# main.net
KiCad netlist of a schematic drawn in EAGLE
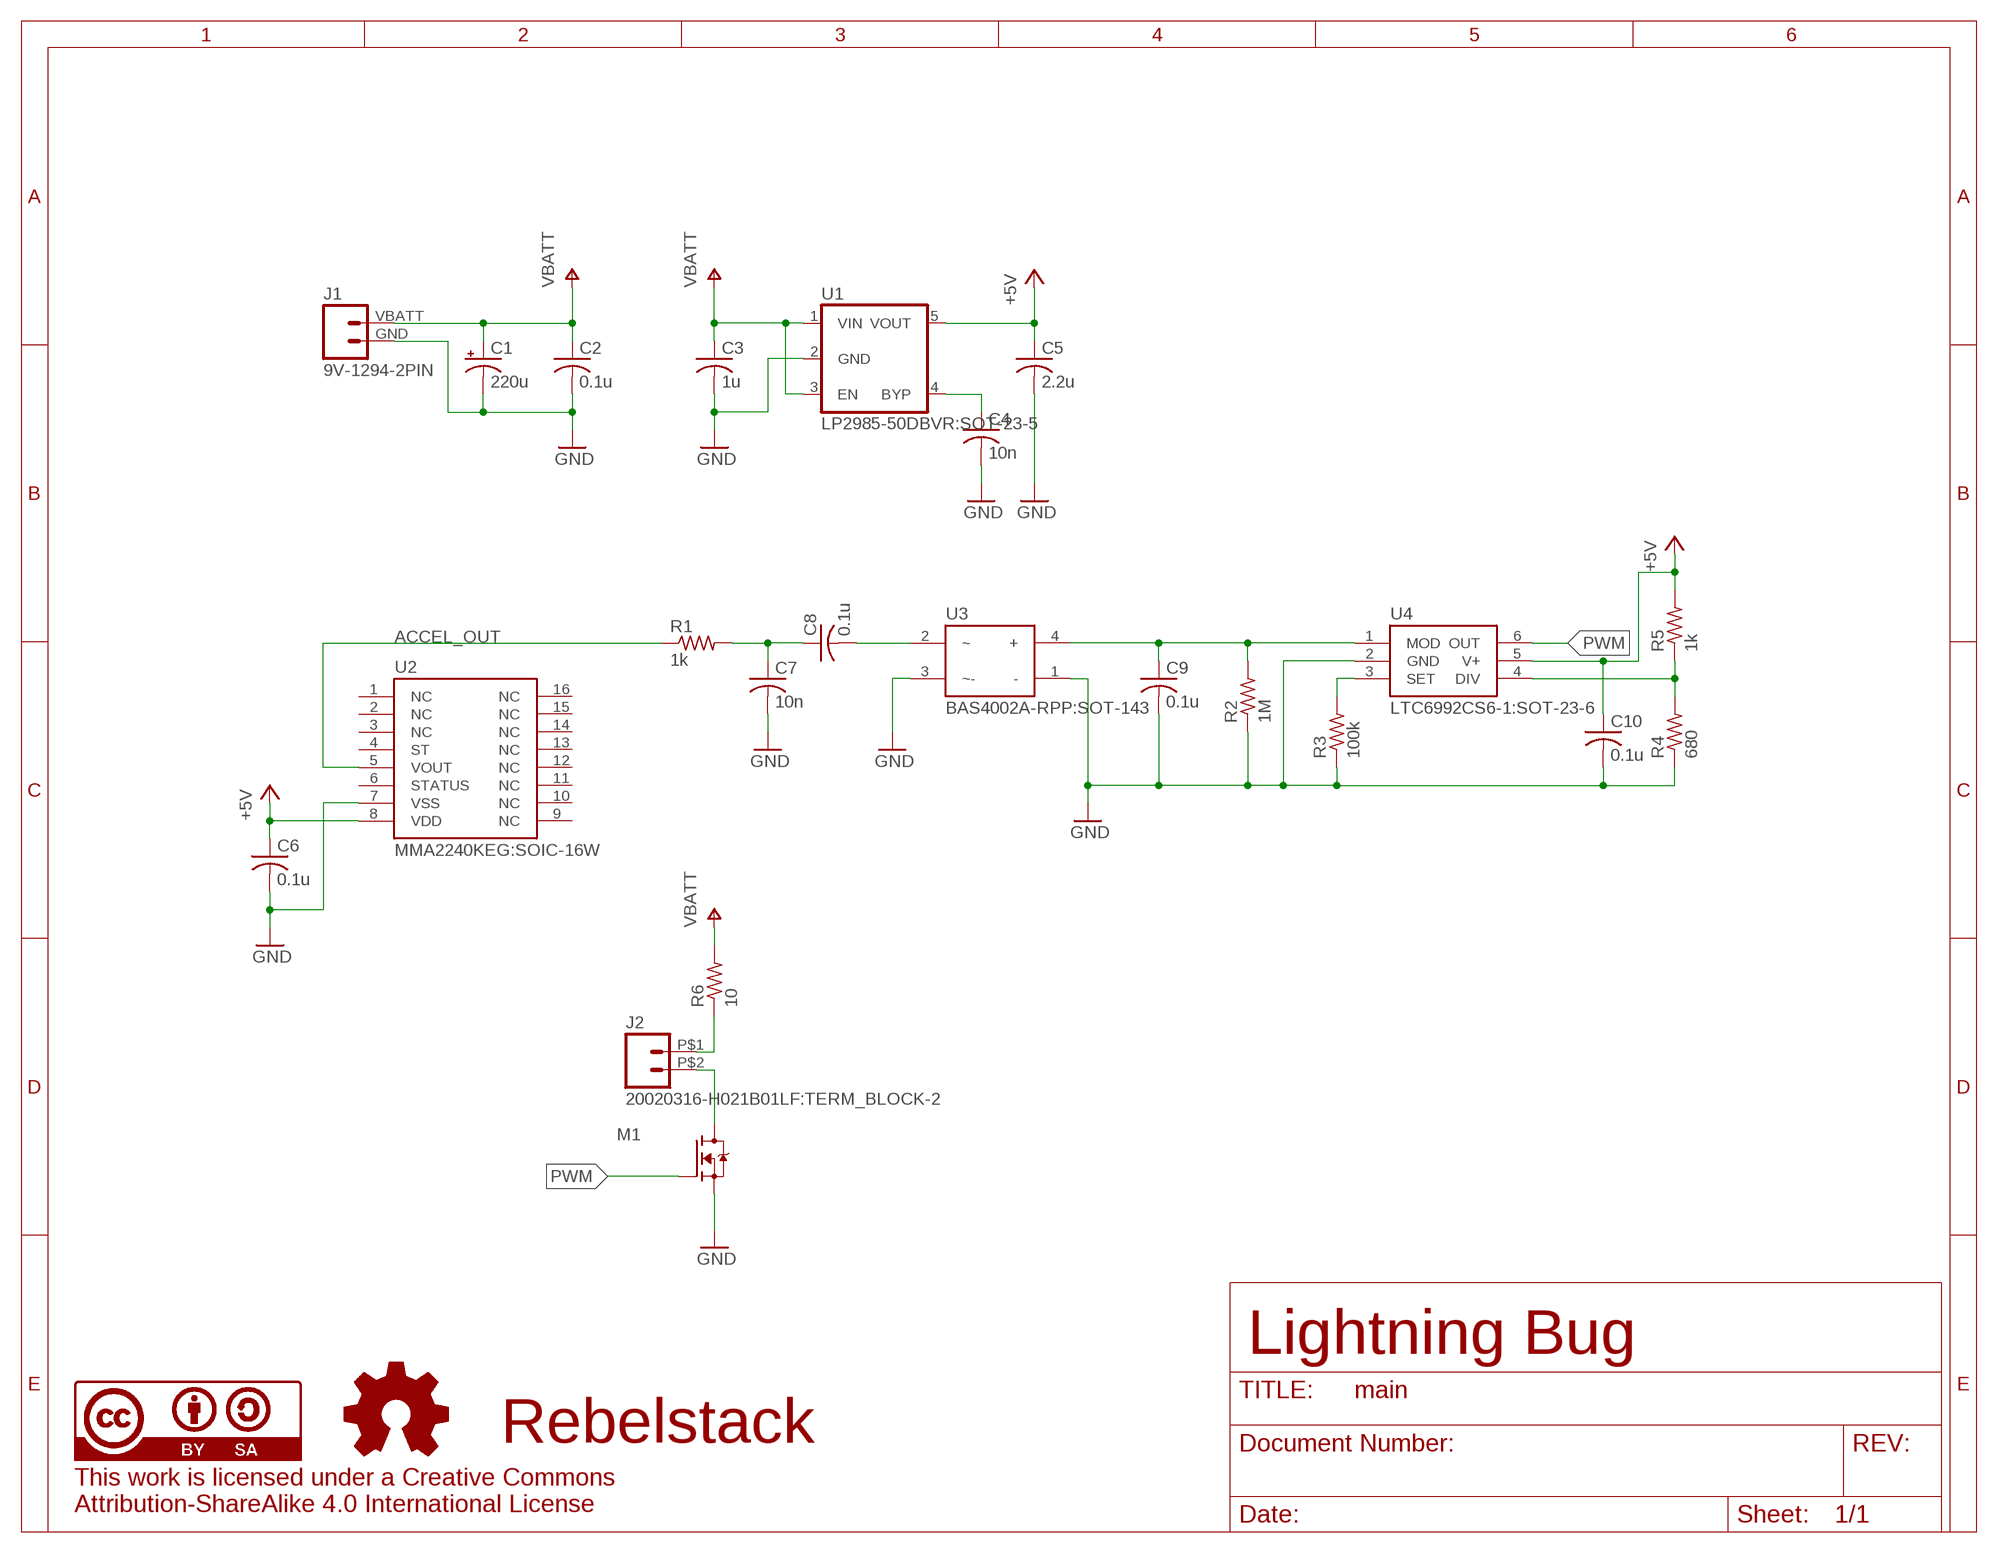
[diagram p0: schematic, sheet 1]

(export (version "E")
  (design (tool "Eeschema 10.0.6"))
  (components
    (comp (ref "C1")
      (value "220u")
      (footprint "eagle-import:D_7343-31W")
      (libsource (lib "eagle-import") (part "CPOL-USD/7343-31W"))
    )
    (comp (ref "C2")
      (value "0.1u")
      (footprint "eagle-import:C0805")
      (libsource (lib "eagle-import") (part "C-USC0805"))
    )
    (comp (ref "C3")
      (value "1u")
      (footprint "eagle-import:C0805")
      (libsource (lib "eagle-import") (part "C-USC0805"))
    )
    (comp (ref "C4")
      (value "10n")
      (footprint "eagle-import:C0805")
      (libsource (lib "eagle-import") (part "C-USC0805"))
    )
    (comp (ref "C5")
      (value "2.2u")
      (footprint "eagle-import:C0805")
      (libsource (lib "eagle-import") (part "C-USC0805"))
    )
    (comp (ref "C6")
      (value "0.1u")
      (footprint "eagle-import:C0805")
      (libsource (lib "eagle-import") (part "C-USC0805"))
    )
    (comp (ref "C7")
      (value "10n")
      (footprint "eagle-import:C0805")
      (libsource (lib "eagle-import") (part "C-USC0805"))
    )
    (comp (ref "C8")
      (value "0.1u")
      (footprint "eagle-import:C0805")
      (libsource (lib "eagle-import") (part "C-USC0805"))
    )
    (comp (ref "C9")
      (value "0.1u")
      (footprint "eagle-import:C0805")
      (libsource (lib "eagle-import") (part "C-USC0805"))
    )
    (comp (ref "C10")
      (value "0.1u")
      (footprint "eagle-import:C0805")
      (libsource (lib "eagle-import") (part "C-USC0805"))
    )
    (comp (ref "J1")
      (value "9V-1294-2PIN")
      (footprint "eagle-import:9V-THRU")
      (libsource (lib "eagle-import") (part "9V-1294-2PIN"))
    )
    (comp (ref "J2")
      (value "20020316-H021B01LF:TERM_BLOCK-2")
      (footprint "eagle-import:TERM_BLOCK-2")
      (libsource (lib "eagle-import") (part "20020316-H021B01LF{colon}TERM_BLOCK-2"))
    )
    (comp (ref "M1")
      (value "IRLML2502TRPBF:SOT-23-3")
      (footprint "eagle-import:SOT-23-3")
      (libsource (lib "eagle-import") (part "IRLML2502TRPBF{colon}SOT-23-3"))
    )
    (comp (ref "R1")
      (value "1k")
      (footprint "eagle-import:M0805")
      (libsource (lib "eagle-import") (part "R-US_M0805"))
    )
    (comp (ref "R2")
      (value "1M")
      (footprint "eagle-import:M0805")
      (libsource (lib "eagle-import") (part "R-US_M0805"))
    )
    (comp (ref "R3")
      (value "100k")
      (footprint "eagle-import:M0805")
      (libsource (lib "eagle-import") (part "R-US_M0805"))
    )
    (comp (ref "R4")
      (value "680")
      (footprint "eagle-import:M0805")
      (libsource (lib "eagle-import") (part "R-US_M0805"))
    )
    (comp (ref "R5")
      (value "1k")
      (footprint "eagle-import:M0805")
      (libsource (lib "eagle-import") (part "R-US_M0805"))
    )
    (comp (ref "R6")
      (value "10")
      (footprint "eagle-import:R2512")
      (libsource (lib "eagle-import") (part "R-US_R2512"))
    )
    (comp (ref "U$4")
      (value "CC-BY-SA-4.0-INT-PCB")
      (footprint "eagle-import:CC-BY-SA-4.0-INT")
      (libsource (lib "eagle-import") (part "CC-BY-SA-4.0-INT-PCB"))
    )
    (comp (ref "U$5")
      (value "OSHW-LOGO-PCB")
      (footprint "eagle-import:OSHW-LOGO")
      (libsource (lib "eagle-import") (part "OSHW-LOGO-PCB"))
    )
    (comp (ref "U1")
      (value "LP2985-50DBVR:SOT-23-5")
      (footprint "eagle-import:SOT-23-5")
      (libsource (lib "eagle-import") (part "LP2985-50DBVR{colon}SOT-23-5"))
    )
    (comp (ref "U2")
      (value "MMA2240KEG:SOIC-16W")
      (footprint "eagle-import:SOIC-16W")
      (libsource (lib "eagle-import") (part "MMA2240KEG{colon}SOIC-16W"))
    )
    (comp (ref "U3")
      (value "BAS4002A-RPP:SOT-143")
      (footprint "eagle-import:SOT-143")
      (libsource (lib "eagle-import") (part "BAS4002A-RPP{colon}SOT-143"))
    )
    (comp (ref "U4")
      (value "LTC6992CS6-1:SOT-23-6")
      (footprint "eagle-import:SOT-23-6")
      (libsource (lib "eagle-import") (part "LTC6992CS6-1{colon}SOT-23-6"))
    )
  )
  (nets
    (net (code "1") (name "+5V") (class "Default")
      (node (ref "C10") (pin "1") (pinfunction "1_1") (pintype "passive"))
      (node (ref "C5") (pin "1") (pinfunction "1_1") (pintype "passive"))
      (node (ref "C6") (pin "1") (pinfunction "1_1") (pintype "passive"))
      (node (ref "R5") (pin "2") (pinfunction "2_2") (pintype "passive"))
      (node (ref "U1") (pin "5") (pinfunction "VOUT_5") (pintype "power_in"))
      (node (ref "U2") (pin "8") (pinfunction "VDD_8") (pintype "passive"))
      (node (ref "U4") (pin "5") (pinfunction "V+_5") (pintype "power_in"))
    )
    (net (code "2") (name "/ACCEL_OUT") (class "Default")
      (node (ref "R1") (pin "1") (pinfunction "1_1") (pintype "passive"))
      (node (ref "U2") (pin "5") (pinfunction "VOUT_5") (pintype "output"))
    )
    (net (code "3") (name "GND") (class "Default")
      (node (ref "C1") (pin "-") (pinfunction "-_-") (pintype "passive"))
      (node (ref "C10") (pin "2") (pinfunction "2_2") (pintype "passive"))
      (node (ref "C2") (pin "2") (pinfunction "2_2") (pintype "passive"))
      (node (ref "C3") (pin "2") (pinfunction "2_2") (pintype "passive"))
      (node (ref "C4") (pin "2") (pinfunction "2_2") (pintype "passive"))
      (node (ref "C5") (pin "2") (pinfunction "2_2") (pintype "passive"))
      (node (ref "C6") (pin "2") (pinfunction "2_2") (pintype "passive"))
      (node (ref "C7") (pin "2") (pinfunction "2_2") (pintype "passive"))
      (node (ref "C9") (pin "2") (pinfunction "2_2") (pintype "passive"))
      (node (ref "J1") (pin "GND") (pinfunction "2_GND") (pintype "power_in"))
      (node (ref "M1") (pin "2") (pinfunction "S_2") (pintype "passive"))
      (node (ref "R2") (pin "1") (pinfunction "1_1") (pintype "passive"))
      (node (ref "R3") (pin "1") (pinfunction "1_1") (pintype "passive"))
      (node (ref "R4") (pin "1") (pinfunction "1_1") (pintype "passive"))
      (node (ref "U1") (pin "2") (pinfunction "GND_2") (pintype "power_in"))
      (node (ref "U2") (pin "7") (pinfunction "VSS_7") (pintype "power_in"))
      (node (ref "U3") (pin "1") (pinfunction "-_1") (pintype "passive"))
      (node (ref "U3") (pin "3") (pinfunction "~{-}_3") (pintype "passive"))
      (node (ref "U4") (pin "2") (pinfunction "GND_2") (pintype "power_in"))
    )
    (net (code "4") (name "Net-(C7-Pad1)") (class "Default")
      (node (ref "C7") (pin "1") (pinfunction "1_1") (pintype "passive"))
      (node (ref "C8") (pin "1") (pinfunction "1_1") (pintype "passive"))
      (node (ref "R1") (pin "2") (pinfunction "2_2") (pintype "passive"))
    )
    (net (code "5") (name "Net-(J2-1)") (class "Default")
      (node (ref "J2") (pin "P$1") (pinfunction "1_P$1") (pintype "passive"))
      (node (ref "R6") (pin "1") (pinfunction "1_1") (pintype "passive"))
    )
    (net (code "6") (name "Net-(J2-2)") (class "Default")
      (node (ref "J2") (pin "P$2") (pinfunction "2_P$2") (pintype "passive"))
      (node (ref "M1") (pin "3") (pinfunction "D_3") (pintype "passive"))
    )
    (net (code "7") (name "Net-(U1-BYP)") (class "Default")
      (node (ref "C4") (pin "1") (pinfunction "1_1") (pintype "passive"))
      (node (ref "U1") (pin "4") (pinfunction "BYP_4") (pintype "passive"))
    )
    (net (code "8") (name "Net-(U3-+)") (class "Default")
      (node (ref "C9") (pin "1") (pinfunction "1_1") (pintype "passive"))
      (node (ref "R2") (pin "2") (pinfunction "2_2") (pintype "passive"))
      (node (ref "U3") (pin "4") (pinfunction "+_4") (pintype "passive"))
      (node (ref "U4") (pin "1") (pinfunction "MOD_1") (pintype "input"))
    )
    (net (code "9") (name "Net-(U3-~)") (class "Default")
      (node (ref "C8") (pin "2") (pinfunction "2_2") (pintype "passive"))
      (node (ref "U3") (pin "2") (pinfunction "~_2") (pintype "passive"))
    )
    (net (code "10") (name "Net-(U4-DIV)") (class "Default")
      (node (ref "R4") (pin "2") (pinfunction "2_2") (pintype "passive"))
      (node (ref "R5") (pin "1") (pinfunction "1_1") (pintype "passive"))
      (node (ref "U4") (pin "4") (pinfunction "DIV_4") (pintype "passive"))
    )
    (net (code "11") (name "Net-(U4-SET)") (class "Default")
      (node (ref "R3") (pin "2") (pinfunction "2_2") (pintype "passive"))
      (node (ref "U4") (pin "3") (pinfunction "SET_3") (pintype "passive"))
    )
    (net (code "12") (name "PWM") (class "Default")
      (node (ref "M1") (pin "1") (pinfunction "G_1") (pintype "passive"))
      (node (ref "U4") (pin "6") (pinfunction "OUT_6") (pintype "output"))
    )
    (net (code "13") (name "VBATT") (class "Default")
      (node (ref "C1") (pin "+") (pinfunction "+_+") (pintype "passive"))
      (node (ref "C2") (pin "1") (pinfunction "1_1") (pintype "passive"))
      (node (ref "C3") (pin "1") (pinfunction "1_1") (pintype "passive"))
      (node (ref "J1") (pin "VBATT") (pinfunction "1_VBATT") (pintype "power_in"))
      (node (ref "R6") (pin "2") (pinfunction "2_2") (pintype "passive"))
      (node (ref "U1") (pin "1") (pinfunction "VIN_1") (pintype "power_in"))
      (node (ref "U1") (pin "3") (pinfunction "EN_3") (pintype "input"))
    )
    (net (code "14") (name "unconnected-(U2-NC-Pad1)") (class "Default")
      (node (ref "U2") (pin "1") (pinfunction "NC_1") (pintype "no_connect"))
    )
    (net (code "15") (name "unconnected-(U2-NC-Pad2)") (class "Default")
      (node (ref "U2") (pin "2") (pinfunction "NC_2") (pintype "no_connect"))
    )
    (net (code "16") (name "unconnected-(U2-NC-Pad3)") (class "Default")
      (node (ref "U2") (pin "3") (pinfunction "NC_3") (pintype "no_connect"))
    )
    (net (code "17") (name "unconnected-(U2-NC-Pad9)") (class "Default")
      (node (ref "U2") (pin "9") (pinfunction "NC_9") (pintype "no_connect"))
    )
    (net (code "18") (name "unconnected-(U2-NC-Pad10)") (class "Default")
      (node (ref "U2") (pin "10") (pinfunction "NC_10") (pintype "no_connect"))
    )
    (net (code "19") (name "unconnected-(U2-NC-Pad11)") (class "Default")
      (node (ref "U2") (pin "11") (pinfunction "NC_11") (pintype "no_connect"))
    )
    (net (code "20") (name "unconnected-(U2-NC-Pad12)") (class "Default")
      (node (ref "U2") (pin "12") (pinfunction "NC_12") (pintype "no_connect"))
    )
    (net (code "21") (name "unconnected-(U2-NC-Pad13)") (class "Default")
      (node (ref "U2") (pin "13") (pinfunction "NC_13") (pintype "no_connect"))
    )
    (net (code "22") (name "unconnected-(U2-NC-Pad14)") (class "Default")
      (node (ref "U2") (pin "14") (pinfunction "NC_14") (pintype "no_connect"))
    )
    (net (code "23") (name "unconnected-(U2-NC-Pad15)") (class "Default")
      (node (ref "U2") (pin "15") (pinfunction "NC_15") (pintype "no_connect"))
    )
    (net (code "24") (name "unconnected-(U2-NC-Pad16)") (class "Default")
      (node (ref "U2") (pin "16") (pinfunction "NC_16") (pintype "no_connect"))
    )
    (net (code "25") (name "unconnected-(U2-ST-Pad4)") (class "Default")
      (node (ref "U2") (pin "4") (pinfunction "ST_4") (pintype "passive"))
    )
    (net (code "26") (name "unconnected-(U2-STATUS-Pad6)") (class "Default")
      (node (ref "U2") (pin "6") (pinfunction "STATUS_6") (pintype "output"))
    )
  )
)
